# rs485.net
KiCad netlist of a schematic drawn in Altium Designer
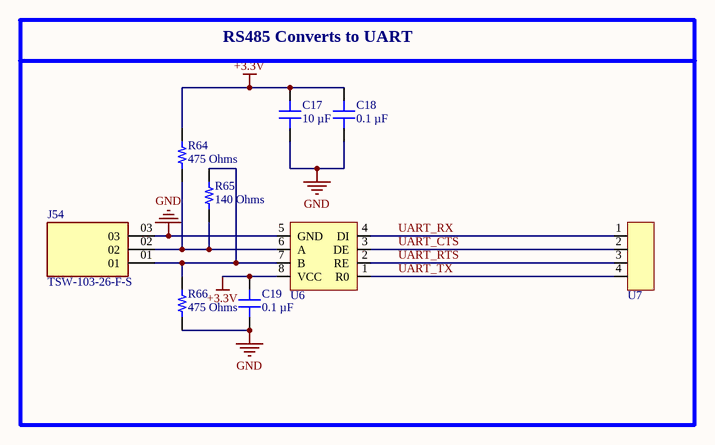
[diagram p0: rs485.SchDoc]

(export (version "E")
  (design (tool "Eeschema 10.0.6"))
  (components
    (comp (ref "C17")
      (value "10 µF")
      (footprint "CAP 0603_1608")
      (description "CAP CER 10UF 6.3V X5R 0603")
      (fields
        (field (name "PART NUMBER") "GRM188R60J106ME47D")
        (field (name "MANUFACTURER") "Murata Electronics")
      )
      (libsource (lib "Celestial Altium Library - altium_library") (part "Capacitor"))
    )
    (comp (ref "C18")
      (value "0.1 µF")
      (footprint "CAP 0603_1608")
      (description "CAP CER 0.1UF 6.3V X7R 0603")
      (fields
        (field (name "PART NUMBER") "6R3X14W104MV4T")
        (field (name "MANUFACTURER") "Johanson Dielectrics Inc.")
      )
      (libsource (lib "Celestial Altium Library - altium_library") (part "Capacitor"))
    )
    (comp (ref "C19")
      (value "0.1 µF")
      (footprint "CAP 0603_1608")
      (description "CAP CER 0.1UF 6.3V X7R 0603")
      (fields
        (field (name "PART NUMBER") "6R3X14W104MV4T")
        (field (name "MANUFACTURER") "Johanson Dielectrics Inc.")
      )
      (libsource (lib "Celestial Altium Library - altium_library") (part "Capacitor"))
    )
    (comp (ref "J54")
      (value "TSW-103-26-F-S")
      (footprint "PcbLib1:SAMTEC_TSW-103-26-F-S")
      (libsource (lib "Schlib1") (part "TSW-103-26-F-S"))
    )
    (comp (ref "R64")
      (value "475 Ohms")
      (footprint "RES 0603_1608")
      (description "RES SMD 475 OHM 0.5% 1/5W 0603")
      (fields
        (field (name "PART NUMBER") "ERJ-PB3D4750V")
        (field (name "MANUFACTURER") "Panasonic Electronic Components")
      )
      (libsource (lib "Celestial Altium Library - altium_library") (part "Resistor"))
    )
    (comp (ref "R65")
      (value "140 Ohms")
      (footprint "RES 0603_1608")
      (description "RES 140 OHM 1% 1/8W 0603")
      (fields
        (field (name "PART NUMBER") "RK73H1JTTD1400F")
        (field (name "MANUFACTURER") "KOA Speer Electronics, Inc.")
      )
      (libsource (lib "Celestial Altium Library - altium_library") (part "Resistor"))
    )
    (comp (ref "R66")
      (value "475 Ohms")
      (footprint "RES 0603_1608")
      (description "RES SMD 475 OHM 0.5% 1/5W 0603")
      (fields
        (field (name "PART NUMBER") "ERJ-PB3D4750V")
        (field (name "MANUFACTURER") "Panasonic Electronic Components")
      )
      (libsource (lib "Celestial Altium Library - altium_library") (part "Resistor"))
    )
    (comp (ref "U6") (value "SP3485") (footprint "SP3485") (libsource (lib "Schlib1") (part "SP3485")))
    (comp (ref "U7")
      (value "Con1x4_WireToWire")
      (footprint "Con1x4_WireToWire")
      (description "1x4P XA 1 2.5mm 4 Copper Alloy Plugin,P=2.5mm Wire To Board / Wire To Wire Connector ROHS")
      (libsource (lib "Schlib1") (part "Con1x4_WireToWire"))
    )
  )
  (nets
    (net (code "1") (name "+3.3V") (class "Default")
      (node (ref "C17") (pin "2") (pinfunction "2_2") (pintype "passive"))
      (node (ref "C18") (pin "2") (pinfunction "2_2") (pintype "passive"))
      (node (ref "C19") (pin "2") (pinfunction "2_2") (pintype "passive"))
      (node (ref "R64") (pin "2") (pinfunction "2_2") (pintype "passive"))
      (node (ref "U6") (pin "8") (pinfunction "VCC_8") (pintype "passive"))
    )
    (net (code "2") (name "/UART_CTS") (class "Default")
      (node (ref "U6") (pin "3") (pinfunction "DE_3") (pintype "passive"))
      (node (ref "U7") (pin "2") (pintype "passive"))
    )
    (net (code "3") (name "/UART_RTS") (class "Default")
      (node (ref "U6") (pin "2") (pinfunction "RE_2") (pintype "passive"))
      (node (ref "U7") (pin "3") (pintype "passive"))
    )
    (net (code "4") (name "/UART_RX") (class "Default")
      (node (ref "U6") (pin "4") (pinfunction "DI_4") (pintype "passive"))
      (node (ref "U7") (pin "1") (pintype "passive"))
    )
    (net (code "5") (name "/UART_TX") (class "Default")
      (node (ref "U6") (pin "1") (pinfunction "R0_1") (pintype "passive"))
      (node (ref "U7") (pin "4") (pintype "passive"))
    )
    (net (code "6") (name "GND") (class "Default")
      (node (ref "C17") (pin "1") (pinfunction "1_1") (pintype "passive"))
      (node (ref "C18") (pin "1") (pinfunction "1_1") (pintype "passive"))
      (node (ref "C19") (pin "1") (pinfunction "1_1") (pintype "passive"))
      (node (ref "J54") (pin "03") (pinfunction "03_03") (pintype "passive"))
      (node (ref "R66") (pin "1") (pinfunction "1_1") (pintype "passive"))
      (node (ref "U6") (pin "5") (pinfunction "GND_5") (pintype "passive"))
    )
    (net (code "7") (name "Net-(U6-A)") (class "Default")
      (node (ref "J54") (pin "02") (pinfunction "02_02") (pintype "passive"))
      (node (ref "R64") (pin "1") (pinfunction "1_1") (pintype "passive"))
      (node (ref "R65") (pin "1") (pinfunction "1_1") (pintype "passive"))
      (node (ref "U6") (pin "6") (pinfunction "A_6") (pintype "passive"))
    )
    (net (code "8") (name "Net-(U6-B)") (class "Default")
      (node (ref "J54") (pin "01") (pinfunction "01_01") (pintype "passive"))
      (node (ref "R65") (pin "2") (pinfunction "2_2") (pintype "passive"))
      (node (ref "R66") (pin "2") (pinfunction "2_2") (pintype "passive"))
      (node (ref "U6") (pin "7") (pinfunction "B_7") (pintype "passive"))
    )
  )
)
